# RS232_NPN_PNP.net
KiCad netlist of a schematic drawn in EAGLE
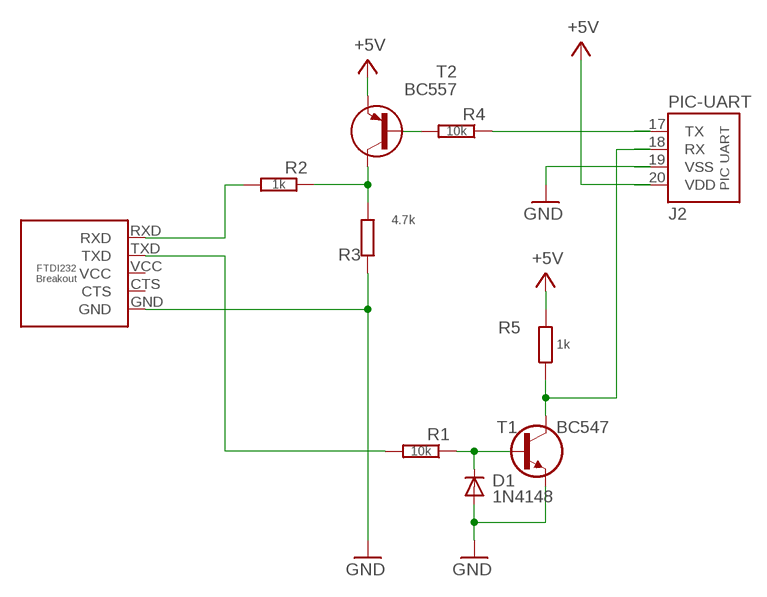
[diagram p0: schematic, sheet 1]

(export (version "E")
  (design (tool "Eeschema 10.0.6"))
  (components
    (comp (ref "D1")
      (value "1N4148")
      (footprint "eagle-import:DO34-5")
      (libsource (lib "eagle-import") (part "1N414834-5"))
    )
    (comp (ref "J1")
      (value "FTDI232")
      (footprint "eagle-import:FTDI232-BO-5-L")
      (libsource (lib "eagle-import") (part "FTDI232-BO-5P-L"))
    )
    (comp (ref "J2")
      (value "PIC-UART")
      (footprint "eagle-import:PIC-UART")
      (libsource (lib "eagle-import") (part "PIC-UART"))
    )
    (comp (ref "R1")
      (value "10k")
      (footprint "eagle-import:0202_5-V")
      (libsource (lib "eagle-import") (part "R0202/5-V"))
    )
    (comp (ref "R2")
      (value "1k")
      (footprint "eagle-import:0202_5-V")
      (libsource (lib "eagle-import") (part "R0202/5-V"))
    )
    (comp (ref "R3")
      (value "4.7k")
      (footprint "eagle-import:0202_5-V")
      (libsource (lib "eagle-import") (part "R0202/5-V"))
    )
    (comp (ref "R4")
      (value "10k")
      (footprint "eagle-import:0202_5")
      (libsource (lib "eagle-import") (part "R0202/5"))
    )
    (comp (ref "R5")
      (value "1k")
      (footprint "eagle-import:0202_5-V")
      (libsource (lib "eagle-import") (part "R0202/5-V"))
    )
    (comp (ref "T1")
      (value "BC547")
      (footprint "eagle-import:TO92-CBE")
      (libsource (lib "eagle-import") (part "BC547CBE"))
    )
    (comp (ref "T2")
      (value "BC557")
      (footprint "eagle-import:TO92-CBE")
      (libsource (lib "eagle-import") (part "BC557CBE"))
    )
  )
  (nets
    (net (code "1") (name "+5V") (class "Default")
      (node (ref "J2") (pin "20") (pinfunction "VDD_20") (pintype "passive"))
      (node (ref "R5") (pin "2") (pinfunction "2_2") (pintype "passive"))
      (node (ref "T2") (pin "E") (pinfunction "E_E") (pintype "passive"))
    )
    (net (code "2") (name "GND") (class "Default")
      (node (ref "D1") (pin "A") (pinfunction "A_A") (pintype "passive"))
      (node (ref "J1") (pin "GND") (pinfunction "GND_GND") (pintype "bidirectional"))
      (node (ref "J2") (pin "19") (pinfunction "VSS_19") (pintype "passive"))
      (node (ref "R3") (pin "1") (pinfunction "1_1") (pintype "passive"))
      (node (ref "T1") (pin "E") (pinfunction "E_E") (pintype "passive"))
    )
    (net (code "3") (name "Net-(D1-PadC)") (class "Default")
      (node (ref "D1") (pin "C") (pinfunction "C_C") (pintype "passive"))
      (node (ref "R1") (pin "1") (pinfunction "1_1") (pintype "passive"))
      (node (ref "T1") (pin "B") (pinfunction "B_B") (pintype "passive"))
    )
    (net (code "4") (name "Net-(J1-PadRXD)") (class "Default")
      (node (ref "J1") (pin "RXD") (pinfunction "RXD_RXD") (pintype "bidirectional"))
      (node (ref "R2") (pin "2") (pinfunction "2_2") (pintype "passive"))
    )
    (net (code "5") (name "Net-(J1-PadTXD)") (class "Default")
      (node (ref "J1") (pin "TXD") (pinfunction "TXD_TXD") (pintype "bidirectional"))
      (node (ref "R1") (pin "2") (pinfunction "2_2") (pintype "passive"))
    )
    (net (code "6") (name "Net-(J2-RX)") (class "Default")
      (node (ref "J2") (pin "18") (pinfunction "RX_18") (pintype "passive"))
      (node (ref "R5") (pin "1") (pinfunction "1_1") (pintype "passive"))
      (node (ref "T1") (pin "C") (pinfunction "C_C") (pintype "passive"))
    )
    (net (code "7") (name "Net-(J2-TX)") (class "Default")
      (node (ref "J2") (pin "17") (pinfunction "TX_17") (pintype "passive"))
      (node (ref "R4") (pin "1") (pinfunction "1_1") (pintype "passive"))
    )
    (net (code "8") (name "Net-(R2-Pad1)") (class "Default")
      (node (ref "R2") (pin "1") (pinfunction "1_1") (pintype "passive"))
      (node (ref "R3") (pin "2") (pinfunction "2_2") (pintype "passive"))
      (node (ref "T2") (pin "C") (pinfunction "C_C") (pintype "passive"))
    )
    (net (code "9") (name "Net-(R4-Pad2)") (class "Default")
      (node (ref "R4") (pin "2") (pinfunction "2_2") (pintype "passive"))
      (node (ref "T2") (pin "B") (pinfunction "B_B") (pintype "passive"))
    )
    (net (code "10") (name "unconnected-(J1-PadCTS)") (class "Default")
      (node (ref "J1") (pin "CTS") (pinfunction "CTS_CTS") (pintype "bidirectional"))
    )
    (net (code "11") (name "unconnected-(J1-PadVCC)") (class "Default")
      (node (ref "J1") (pin "VCC") (pinfunction "VCC_VCC") (pintype "bidirectional"))
    )
  )
)
